# dacmo.net
KiCad netlist of a schematic drawn in EAGLE
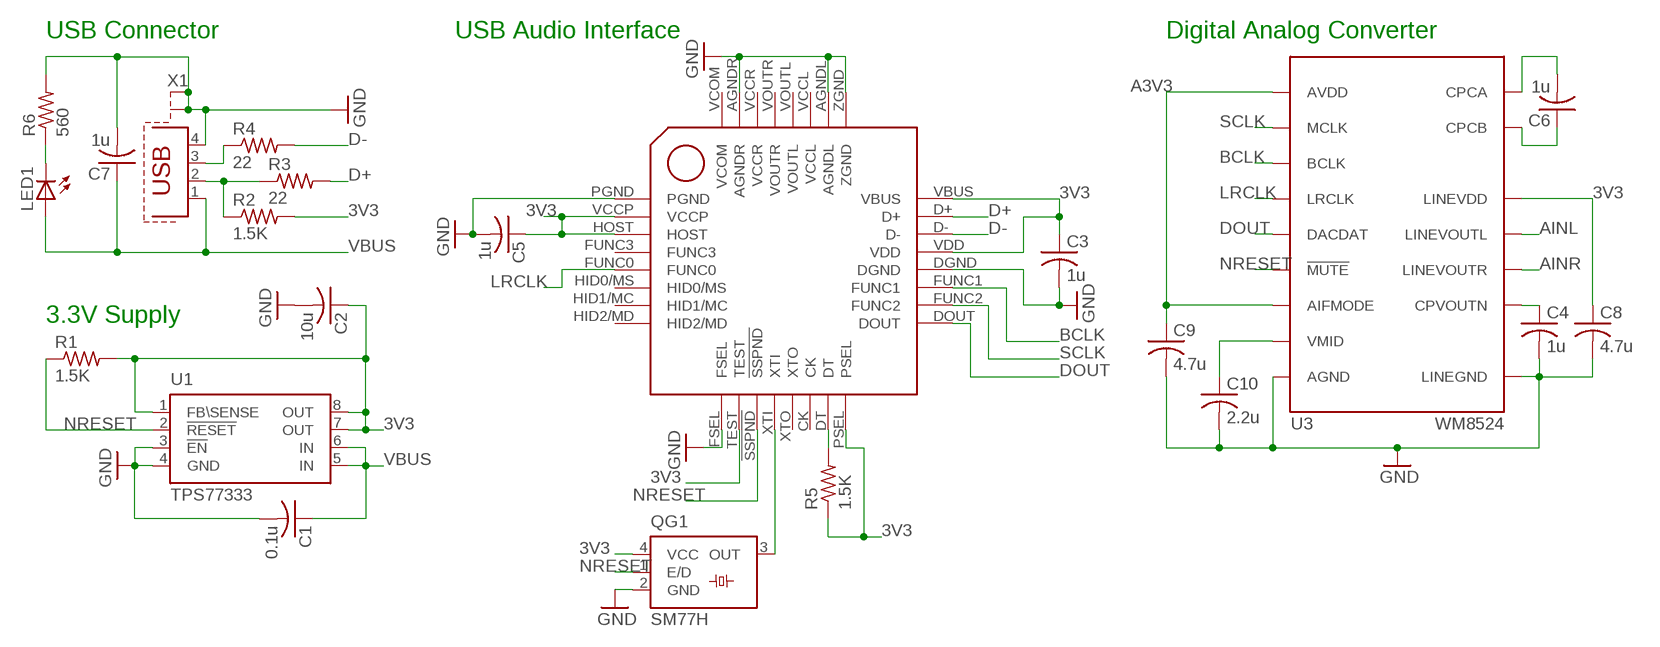
[diagram p0: schematic, sheet 1]

(export (version "E")
  (design (tool "Eeschema 10.0.6"))
  (components
    (comp (ref "C1")
      (value "0.1u")
      (footprint "eagle-import:C0805")
      (libsource (lib "eagle-import") (part "C-USC0805"))
    )
    (comp (ref "C2")
      (value "10u")
      (footprint "eagle-import:C0805")
      (libsource (lib "eagle-import") (part "C-USC0805"))
    )
    (comp (ref "C3")
      (value "1u")
      (footprint "eagle-import:C0805")
      (libsource (lib "eagle-import") (part "C-USC0805"))
    )
    (comp (ref "C4")
      (value "1u")
      (footprint "eagle-import:C0805")
      (libsource (lib "eagle-import") (part "C-USC0805"))
    )
    (comp (ref "C5")
      (value "1u")
      (footprint "eagle-import:C0805")
      (libsource (lib "eagle-import") (part "C-USC0805"))
    )
    (comp (ref "C6")
      (value "1u")
      (footprint "eagle-import:C0805")
      (libsource (lib "eagle-import") (part "C-USC0805"))
    )
    (comp (ref "C7")
      (value "1u")
      (footprint "eagle-import:C0805")
      (libsource (lib "eagle-import") (part "C-USC0805"))
    )
    (comp (ref "C8")
      (value "4.7u")
      (footprint "eagle-import:C0805")
      (libsource (lib "eagle-import") (part "C-USC0805"))
    )
    (comp (ref "C9")
      (value "4.7u")
      (footprint "eagle-import:C0805")
      (libsource (lib "eagle-import") (part "C-USC0805"))
    )
    (comp (ref "C10")
      (value "2.2u")
      (footprint "eagle-import:C0805")
      (libsource (lib "eagle-import") (part "C-USC0805"))
    )
    (comp (ref "LED1")
      (value "LEDCHIP-LED0805")
      (footprint "eagle-import:CHIP-LED0805")
      (libsource (lib "eagle-import") (part "LEDCHIP-LED0805"))
    )
    (comp (ref "QG1")
      (value "SM77H")
      (footprint "eagle-import:SM77H")
      (libsource (lib "eagle-import") (part "SM77H"))
    )
    (comp (ref "R1")
      (value "1.5K")
      (footprint "eagle-import:R0805")
      (libsource (lib "eagle-import") (part "R-US_R0805"))
    )
    (comp (ref "R2")
      (value "1.5K")
      (footprint "eagle-import:R0805")
      (libsource (lib "eagle-import") (part "R-US_R0805"))
    )
    (comp (ref "R3")
      (value "22")
      (footprint "eagle-import:R0805")
      (libsource (lib "eagle-import") (part "R-US_R0805"))
    )
    (comp (ref "R4")
      (value "22")
      (footprint "eagle-import:R0805")
      (libsource (lib "eagle-import") (part "R-US_R0805"))
    )
    (comp (ref "R5")
      (value "1.5K")
      (footprint "eagle-import:R0805")
      (libsource (lib "eagle-import") (part "R-US_R0805"))
    )
    (comp (ref "R6")
      (value "560")
      (footprint "eagle-import:R0805")
      (libsource (lib "eagle-import") (part "R-US_R0805"))
    )
    (comp (ref "U1")
      (value "TPS77333")
      (footprint "eagle-import:SOP-08")
      (fields (field (name "MF") "TEXAS INSTRUMENTS") (field (name "MPN") "TPS77333DGK"))
      (libsource (lib "eagle-import") (part "TPS77333"))
    )
    (comp (ref "U2")
      (value "PCM2706")
      (footprint "eagle-import:TQFP32-08")
      (libsource (lib "eagle-import") (part "PCM2706"))
    )
    (comp (ref "U3")
      (value "WM8524")
      (footprint "eagle-import:SSOP16")
      (libsource (lib "eagle-import") (part "WM8524"))
    )
    (comp (ref "X1")
      (value "PN61729-S")
      (footprint "eagle-import:PN61729-S")
      (libsource (lib "eagle-import") (part "PN61729-S"))
    )
  )
  (nets
    (net (code "1") (name "/3V3") (class "Default")
      (node (ref "C2") (pin "1") (pinfunction "1_1") (pintype "passive"))
      (node (ref "C3") (pin "1") (pinfunction "1_1") (pintype "passive"))
      (node (ref "C5") (pin "1") (pinfunction "1_1") (pintype "passive"))
      (node (ref "C8") (pin "1") (pinfunction "1_1") (pintype "passive"))
      (node (ref "QG1") (pin "4") (pinfunction "VCC_4") (pintype "power_in"))
      (node (ref "R1") (pin "2") (pinfunction "2_2") (pintype "passive"))
      (node (ref "R2") (pin "2") (pinfunction "2_2") (pintype "passive"))
      (node (ref "R5") (pin "1") (pinfunction "1_1") (pintype "passive"))
      (node (ref "U1") (pin "1") (pinfunction "FB\\SENSE_1") (pintype "input"))
      (node (ref "U1") (pin "7") (pinfunction "OUT_7") (pintype "output"))
      (node (ref "U1") (pin "8") (pinfunction "OUT_8") (pintype "passive"))
      (node (ref "U2") (pin "HOST") (pinfunction "HOST_HOST") (pintype "power_in"))
      (node (ref "U2") (pin "PSEL") (pinfunction "PSEL_PSEL") (pintype "bidirectional"))
      (node (ref "U2") (pin "TEST") (pinfunction "TEST_TEST") (pintype "bidirectional"))
      (node (ref "U2") (pin "VBUS") (pinfunction "VBUS_VBUS") (pintype "power_in"))
      (node (ref "U2") (pin "VCCP") (pinfunction "VCCP_VCCP") (pintype "power_in"))
      (node (ref "U2") (pin "VDD") (pinfunction "VDD_VDD") (pintype "power_in"))
      (node (ref "U3") (pin "6") (pinfunction "LINEVDD_6") (pintype "power_in"))
    )
    (net (code "2") (name "/A3V3") (class "Default")
      (node (ref "C9") (pin "1") (pinfunction "1_1") (pintype "passive"))
      (node (ref "U3") (pin "12") (pinfunction "AIFMODE_12") (pintype "input"))
      (node (ref "U3") (pin "15") (pinfunction "AVDD_15") (pintype "power_in"))
    )
    (net (code "3") (name "/AINL") (class "Default")
      (node (ref "U3") (pin "1") (pinfunction "LINEVOUTL_1") (pintype "output"))
    )
    (net (code "4") (name "/AINR") (class "Default")
      (node (ref "U3") (pin "16") (pinfunction "LINEVOUTR_16") (pintype "output"))
    )
    (net (code "5") (name "/BCLK") (class "Default")
      (node (ref "U2") (pin "FUNC1") (pinfunction "FUNC1_FUNC1") (pintype "bidirectional"))
      (node (ref "U3") (pin "9") (pinfunction "BCLK_9") (pintype "input"))
    )
    (net (code "6") (name "/D+") (class "Default")
      (node (ref "R3") (pin "2") (pinfunction "2_2") (pintype "passive"))
      (node (ref "U2") (pin "D+") (pinfunction "D+_D+") (pintype "bidirectional"))
    )
    (net (code "7") (name "/D-") (class "Default")
      (node (ref "R4") (pin "2") (pinfunction "2_2") (pintype "passive"))
      (node (ref "U2") (pin "D-") (pinfunction "D-_D-") (pintype "bidirectional"))
    )
    (net (code "8") (name "/DOUT") (class "Default")
      (node (ref "U2") (pin "DOUT") (pinfunction "DOUT_DOUT") (pintype "bidirectional"))
      (node (ref "U3") (pin "7") (pinfunction "DACDAT_7") (pintype "input"))
    )
    (net (code "9") (name "/LRCLK") (class "Default")
      (node (ref "U2") (pin "FUNC0") (pinfunction "FUNC0_FUNC0") (pintype "bidirectional"))
      (node (ref "U3") (pin "8") (pinfunction "LRCLK_8") (pintype "input"))
    )
    (net (code "10") (name "/NRESET") (class "Default")
      (node (ref "QG1") (pin "1") (pinfunction "E/D_1") (pintype "input"))
      (node (ref "R1") (pin "1") (pinfunction "1_1") (pintype "passive"))
      (node (ref "U1") (pin "2") (pinfunction "~{RESET}_2") (pintype "input"))
      (node (ref "U2") (pin "!SSPND") (pinfunction "~{SSPND}_!SSPND") (pintype "bidirectional"))
      (node (ref "U3") (pin "11") (pinfunction "~{MUTE}_11") (pintype "input"))
    )
    (net (code "11") (name "/SCLK") (class "Default")
      (node (ref "U2") (pin "FUNC2") (pinfunction "FUNC2_FUNC2") (pintype "bidirectional"))
      (node (ref "U3") (pin "10") (pinfunction "MCLK_10") (pintype "input"))
    )
    (net (code "12") (name "/VBUS") (class "Default")
      (node (ref "C1") (pin "1") (pinfunction "1_1") (pintype "passive"))
      (node (ref "C7") (pin "1") (pinfunction "1_1") (pintype "passive"))
      (node (ref "LED1") (pin "A") (pinfunction "A_A") (pintype "passive"))
      (node (ref "U1") (pin "5") (pinfunction "IN_5") (pintype "input"))
      (node (ref "U1") (pin "6") (pinfunction "IN_6") (pintype "input"))
      (node (ref "X1") (pin "1") (pinfunction "1_1") (pintype "passive"))
    )
    (net (code "13") (name "/VCCL") (class "Default")
      (node (ref "U2") (pin "VCCL") (pinfunction "VCCL_VCCL") (pintype "power_in"))
    )
    (net (code "14") (name "/VCCR") (class "Default")
      (node (ref "U2") (pin "VCCR") (pinfunction "VCCR_VCCR") (pintype "power_in"))
    )
    (net (code "15") (name "/VCOM") (class "Default")
      (node (ref "U2") (pin "VCOM") (pinfunction "VCOM_VCOM") (pintype "power_in"))
    )
    (net (code "16") (name "GND") (class "Default")
      (node (ref "C1") (pin "2") (pinfunction "2_2") (pintype "passive"))
      (node (ref "C10") (pin "2") (pinfunction "2_2") (pintype "passive"))
      (node (ref "C2") (pin "2") (pinfunction "2_2") (pintype "passive"))
      (node (ref "C3") (pin "2") (pinfunction "2_2") (pintype "passive"))
      (node (ref "C4") (pin "2") (pinfunction "2_2") (pintype "passive"))
      (node (ref "C5") (pin "2") (pinfunction "2_2") (pintype "passive"))
      (node (ref "C7") (pin "2") (pinfunction "2_2") (pintype "passive"))
      (node (ref "C8") (pin "2") (pinfunction "2_2") (pintype "passive"))
      (node (ref "C9") (pin "2") (pinfunction "2_2") (pintype "passive"))
      (node (ref "QG1") (pin "2") (pinfunction "GND_2") (pintype "power_in"))
      (node (ref "R6") (pin "2") (pinfunction "2_2") (pintype "passive"))
      (node (ref "U1") (pin "3") (pinfunction "~{EN}_3") (pintype "input"))
      (node (ref "U1") (pin "4") (pinfunction "GND_4") (pintype "power_in"))
      (node (ref "U2") (pin "AGNDL") (pinfunction "AGNDL_AGNDL") (pintype "power_in"))
      (node (ref "U2") (pin "AGNDR") (pinfunction "AGNDR_AGNDR") (pintype "power_in"))
      (node (ref "U2") (pin "DGND") (pinfunction "DGND_DGND") (pintype "power_in"))
      (node (ref "U2") (pin "FSEL") (pinfunction "FSEL_FSEL") (pintype "bidirectional"))
      (node (ref "U2") (pin "PGND") (pinfunction "PGND_PGND") (pintype "power_in"))
      (node (ref "U2") (pin "ZGND") (pinfunction "ZGND_ZGND") (pintype "power_in"))
      (node (ref "U3") (pin "13") (pinfunction "AGND_13") (pintype "power_in"))
      (node (ref "U3") (pin "4") (pinfunction "LINEGND_4") (pintype "power_in"))
      (node (ref "X1") (pin "4") (pinfunction "4_4") (pintype "passive"))
      (node (ref "X1") (pin "S1") (pinfunction "S1_S1") (pintype "passive"))
      (node (ref "X1") (pin "S2") (pinfunction "S2_S2") (pintype "passive"))
    )
    (net (code "17") (name "Net-(LED1-PadC)") (class "Default")
      (node (ref "LED1") (pin "C") (pinfunction "C_C") (pintype "passive"))
      (node (ref "R6") (pin "1") (pinfunction "1_1") (pintype "passive"))
    )
    (net (code "18") (name "Net-(QG1-OUT)") (class "Default")
      (node (ref "QG1") (pin "3") (pinfunction "OUT_3") (pintype "output"))
      (node (ref "U2") (pin "XTI") (pinfunction "XTI_XTI") (pintype "bidirectional"))
    )
    (net (code "19") (name "Net-(R2-Pad1)") (class "Default")
      (node (ref "R2") (pin "1") (pinfunction "1_1") (pintype "passive"))
      (node (ref "R3") (pin "1") (pinfunction "1_1") (pintype "passive"))
      (node (ref "X1") (pin "2") (pinfunction "2_2") (pintype "passive"))
    )
    (net (code "20") (name "Net-(R4-Pad1)") (class "Default")
      (node (ref "R4") (pin "1") (pinfunction "1_1") (pintype "passive"))
      (node (ref "X1") (pin "3") (pinfunction "3_3") (pintype "passive"))
    )
    (net (code "21") (name "Net-(R5-Pad2)") (class "Default")
      (node (ref "R5") (pin "2") (pinfunction "2_2") (pintype "passive"))
      (node (ref "U2") (pin "DT") (pinfunction "DT_DT") (pintype "bidirectional"))
    )
    (net (code "22") (name "Net-(U3-CPCA)") (class "Default")
      (node (ref "C6") (pin "2") (pinfunction "2_2") (pintype "passive"))
      (node (ref "U3") (pin "5") (pinfunction "CPCA_5") (pintype "passive"))
    )
    (net (code "23") (name "Net-(U3-CPCB)") (class "Default")
      (node (ref "C6") (pin "1") (pinfunction "1_1") (pintype "passive"))
      (node (ref "U3") (pin "3") (pinfunction "CPCB_3") (pintype "passive"))
    )
    (net (code "24") (name "Net-(U3-CPVOUTN)") (class "Default")
      (node (ref "C4") (pin "1") (pinfunction "1_1") (pintype "passive"))
      (node (ref "U3") (pin "2") (pinfunction "CPVOUTN_2") (pintype "power_in"))
    )
    (net (code "25") (name "Net-(U3-VMID)") (class "Default")
      (node (ref "C10") (pin "1") (pinfunction "1_1") (pintype "passive"))
      (node (ref "U3") (pin "14") (pinfunction "VMID_14") (pintype "power_in"))
    )
    (net (code "26") (name "unconnected-(U2-PadCK)") (class "Default")
      (node (ref "U2") (pin "CK") (pinfunction "CK_CK") (pintype "bidirectional"))
    )
    (net (code "27") (name "unconnected-(U2-PadFUNC3)") (class "Default")
      (node (ref "U2") (pin "FUNC3") (pinfunction "FUNC3_FUNC3") (pintype "bidirectional"))
    )
    (net (code "28") (name "unconnected-(U2-PadHID0{slash}MS)") (class "Default")
      (node (ref "U2") (pin "HID0/MS") (pinfunction "HID0/MS_HID0/MS") (pintype "bidirectional"))
    )
    (net (code "29") (name "unconnected-(U2-PadHID1{slash}MC)") (class "Default")
      (node (ref "U2") (pin "HID1/MC") (pinfunction "HID1/MC_HID1/MC") (pintype "bidirectional"))
    )
    (net (code "30") (name "unconnected-(U2-PadHID2{slash}MD)") (class "Default")
      (node (ref "U2") (pin "HID2/MD") (pinfunction "HID2/MD_HID2/MD") (pintype "bidirectional"))
    )
    (net (code "31") (name "unconnected-(U2-PadVOUTL)") (class "Default")
      (node (ref "U2") (pin "VOUTL") (pinfunction "VOUTL_VOUTL") (pintype "output"))
    )
    (net (code "32") (name "unconnected-(U2-PadVOUTR)") (class "Default")
      (node (ref "U2") (pin "VOUTR") (pinfunction "VOUTR_VOUTR") (pintype "output"))
    )
    (net (code "33") (name "unconnected-(U2-PadXTO)") (class "Default")
      (node (ref "U2") (pin "XTO") (pinfunction "XTO_XTO") (pintype "bidirectional"))
    )
  )
)
